# garden.net
KiCad netlist of a schematic drawn in EAGLE
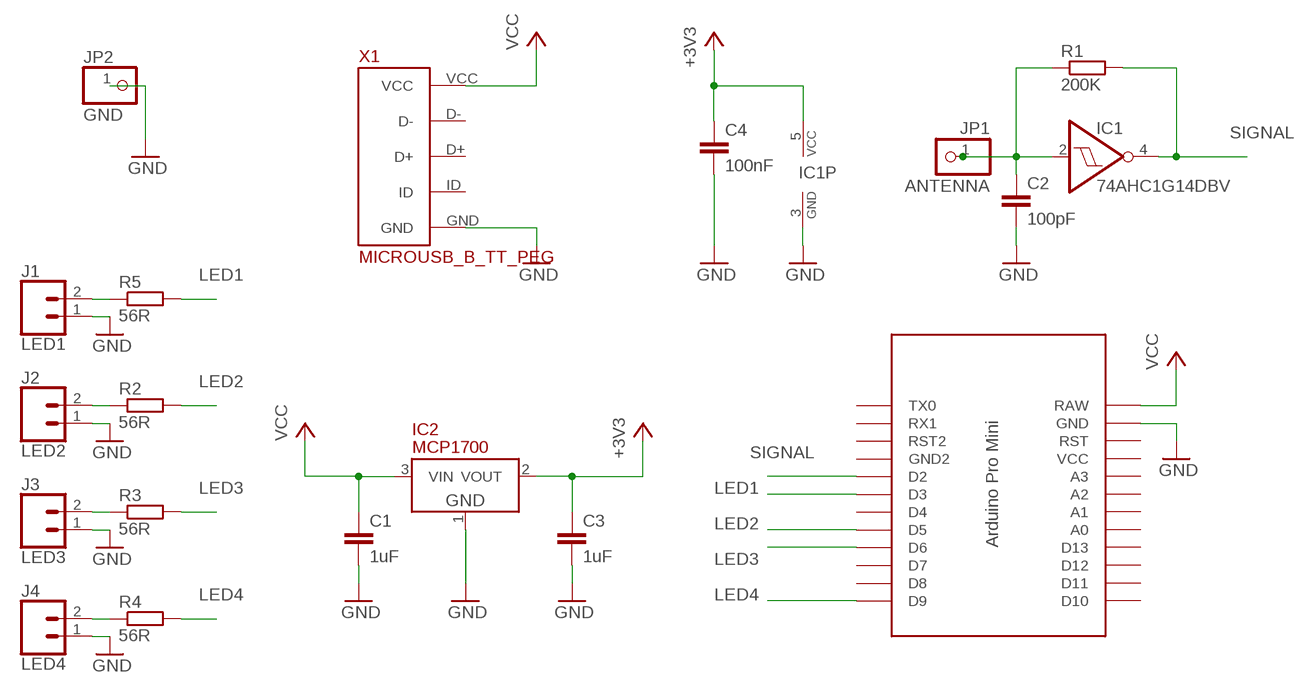
[diagram p0: schematic, sheet 1]

(export (version "E")
  (design (tool "Eeschema 10.0.6"))
  (components
    (comp (ref "C1")
      (value "1uF")
      (footprint "eagle-import:C0805")
      (libsource (lib "eagle-import") (part "C-EUC0805"))
    )
    (comp (ref "C2")
      (value "100pF")
      (footprint "eagle-import:C0805")
      (libsource (lib "eagle-import") (part "C-EUC0805"))
    )
    (comp (ref "C3")
      (value "1uF")
      (footprint "eagle-import:C0805")
      (libsource (lib "eagle-import") (part "C-EUC0805"))
    )
    (comp (ref "C4")
      (value "100nF")
      (footprint "eagle-import:C0805")
      (libsource (lib "eagle-import") (part "C-EUC0805"))
    )
    (comp (ref "IC1")
      (value "74AHC1G14DBV")
      (footprint "eagle-import:SOT23-5")
      (libsource (lib "eagle-import") (part "741G14DBVAHC"))
    )
    (comp (ref "IC2")
      (value "MCP1700")
      (footprint "eagle-import:SOT-23")
      (libsource (lib "eagle-import") (part "MCP1700"))
    )
    (comp (ref "J1")
      (value "LED1")
      (footprint "eagle-import:1X02")
      (libsource (lib "eagle-import") (part "CONN_02"))
    )
    (comp (ref "J2")
      (value "LED2")
      (footprint "eagle-import:1X02")
      (libsource (lib "eagle-import") (part "CONN_02"))
    )
    (comp (ref "J3")
      (value "LED3")
      (footprint "eagle-import:1X02")
      (libsource (lib "eagle-import") (part "CONN_02"))
    )
    (comp (ref "J4")
      (value "LED4")
      (footprint "eagle-import:1X02")
      (libsource (lib "eagle-import") (part "CONN_02"))
    )
    (comp (ref "JP1")
      (value "ANTENNA")
      (footprint "eagle-import:1X01")
      (libsource (lib "eagle-import") (part "PINHD-1X1"))
    )
    (comp (ref "JP2")
      (value "GND")
      (footprint "eagle-import:1X01")
      (libsource (lib "eagle-import") (part "PINHD-1X1"))
    )
    (comp (ref "R1")
      (value "200K")
      (footprint "eagle-import:R0805")
      (libsource (lib "eagle-import") (part "resistor_R-EU_R0805"))
    )
    (comp (ref "R2")
      (value "56R")
      (footprint "eagle-import:M0805")
      (libsource (lib "eagle-import") (part "R-EU_M0805"))
    )
    (comp (ref "R3")
      (value "56R")
      (footprint "eagle-import:M0805")
      (libsource (lib "eagle-import") (part "R-EU_M0805"))
    )
    (comp (ref "R4")
      (value "56R")
      (footprint "eagle-import:M0805")
      (libsource (lib "eagle-import") (part "R-EU_M0805"))
    )
    (comp (ref "R5")
      (value "56R")
      (footprint "eagle-import:M0805")
      (libsource (lib "eagle-import") (part "R-EU_M0805"))
    )
    (comp (ref "U$1")
      (value "PRO-MINI-TWO-SIDES-ONLY")
      (footprint "eagle-import:PRO-MINI-TWO-SIDES-ONLY")
      (libsource (lib "eagle-import") (part "PRO-MINI-TWO-SIDES-ONLY"))
    )
    (comp (ref "X1")
      (value "MICROUSB_B_TT_PEG")
      (footprint "eagle-import:MICROUSB_B_TT_PEG")
      (libsource (lib "eagle-import") (part "MICROUSB_B_TT_PEG"))
    )
  )
  (nets
    (net (code "1") (name "+3V3") (class "Default")
      (node (ref "C3") (pin "1") (pinfunction "1_1") (pintype "passive"))
      (node (ref "C4") (pin "1") (pinfunction "1_1") (pintype "passive"))
      (node (ref "IC1") (pin "5") (pinfunction "VCC_5") (pintype "power_in"))
      (node (ref "IC2") (pin "2") (pinfunction "VOUT_2") (pintype "passive"))
    )
    (net (code "2") (name "/LED1") (class "Default")
      (node (ref "R5") (pin "2") (pinfunction "2_2") (pintype "passive"))
      (node (ref "U$1") (pin "D3") (pinfunction "D3_D3") (pintype "bidirectional"))
    )
    (net (code "3") (name "/LED2") (class "Default")
      (node (ref "R2") (pin "2") (pinfunction "2_2") (pintype "passive"))
      (node (ref "U$1") (pin "D5") (pinfunction "D5_D5") (pintype "bidirectional"))
    )
    (net (code "4") (name "/LED3") (class "Default")
      (node (ref "R3") (pin "2") (pinfunction "2_2") (pintype "passive"))
      (node (ref "U$1") (pin "D6") (pinfunction "D6_D6") (pintype "bidirectional"))
    )
    (net (code "5") (name "/LED4") (class "Default")
      (node (ref "R4") (pin "2") (pinfunction "2_2") (pintype "passive"))
      (node (ref "U$1") (pin "D9") (pinfunction "D9_D9") (pintype "bidirectional"))
    )
    (net (code "6") (name "/SIGNAL") (class "Default")
      (node (ref "IC1") (pin "4") (pinfunction "O_4") (pintype "output"))
      (node (ref "R1") (pin "2") (pinfunction "2_2") (pintype "passive"))
      (node (ref "U$1") (pin "D2") (pinfunction "D2_D2") (pintype "bidirectional"))
    )
    (net (code "7") (name "GND") (class "Default")
      (node (ref "C1") (pin "2") (pinfunction "2_2") (pintype "passive"))
      (node (ref "C2") (pin "2") (pinfunction "2_2") (pintype "passive"))
      (node (ref "C3") (pin "2") (pinfunction "2_2") (pintype "passive"))
      (node (ref "C4") (pin "2") (pinfunction "2_2") (pintype "passive"))
      (node (ref "IC1") (pin "3") (pinfunction "GND_3") (pintype "power_in"))
      (node (ref "IC2") (pin "1") (pinfunction "GND_1") (pintype "input"))
      (node (ref "J1") (pin "1") (pinfunction "1_1") (pintype "passive"))
      (node (ref "J2") (pin "1") (pinfunction "1_1") (pintype "passive"))
      (node (ref "J3") (pin "1") (pinfunction "1_1") (pintype "passive"))
      (node (ref "J4") (pin "1") (pinfunction "1_1") (pintype "passive"))
      (node (ref "JP2") (pin "1") (pinfunction "1_1") (pintype "passive"))
      (node (ref "U$1") (pin "GND") (pinfunction "GND_GND") (pintype "input"))
      (node (ref "X1") (pin "GND") (pinfunction "GND_GND") (pintype "power_in"))
    )
    (net (code "8") (name "Net-(IC1A-I)") (class "Default")
      (node (ref "C2") (pin "1") (pinfunction "1_1") (pintype "passive"))
      (node (ref "IC1") (pin "2") (pinfunction "I_2") (pintype "input"))
      (node (ref "JP1") (pin "1") (pinfunction "1_1") (pintype "passive"))
      (node (ref "R1") (pin "1") (pinfunction "1_1") (pintype "passive"))
    )
    (net (code "9") (name "Net-(J1-Pad2)") (class "Default")
      (node (ref "J1") (pin "2") (pinfunction "2_2") (pintype "passive"))
      (node (ref "R5") (pin "1") (pinfunction "1_1") (pintype "passive"))
    )
    (net (code "10") (name "Net-(J2-Pad2)") (class "Default")
      (node (ref "J2") (pin "2") (pinfunction "2_2") (pintype "passive"))
      (node (ref "R2") (pin "1") (pinfunction "1_1") (pintype "passive"))
    )
    (net (code "11") (name "Net-(J3-Pad2)") (class "Default")
      (node (ref "J3") (pin "2") (pinfunction "2_2") (pintype "passive"))
      (node (ref "R3") (pin "1") (pinfunction "1_1") (pintype "passive"))
    )
    (net (code "12") (name "Net-(J4-Pad2)") (class "Default")
      (node (ref "J4") (pin "2") (pinfunction "2_2") (pintype "passive"))
      (node (ref "R4") (pin "1") (pinfunction "1_1") (pintype "passive"))
    )
    (net (code "13") (name "VCC") (class "Default")
      (node (ref "C1") (pin "1") (pinfunction "1_1") (pintype "passive"))
      (node (ref "IC2") (pin "3") (pinfunction "VIN_3") (pintype "input"))
      (node (ref "U$1") (pin "RAW") (pinfunction "RAW_RAW") (pintype "power_in"))
      (node (ref "X1") (pin "VCC") (pinfunction "VCC_VCC") (pintype "power_in"))
    )
    (net (code "14") (name "unconnected-(U$1-GND2-PadGND1)") (class "Default")
      (node (ref "U$1") (pin "GND1") (pinfunction "GND2_GND1") (pintype "bidirectional"))
    )
    (net (code "15") (name "unconnected-(U$1-PadA0)") (class "Default")
      (node (ref "U$1") (pin "A0") (pinfunction "A0_A0") (pintype "bidirectional"))
    )
    (net (code "16") (name "unconnected-(U$1-PadA1)") (class "Default")
      (node (ref "U$1") (pin "A1") (pinfunction "A1_A1") (pintype "bidirectional"))
    )
    (net (code "17") (name "unconnected-(U$1-PadA2)") (class "Default")
      (node (ref "U$1") (pin "A2") (pinfunction "A2_A2") (pintype "bidirectional"))
    )
    (net (code "18") (name "unconnected-(U$1-PadA3)") (class "Default")
      (node (ref "U$1") (pin "A3") (pinfunction "A3_A3") (pintype "bidirectional"))
    )
    (net (code "19") (name "unconnected-(U$1-PadD4)") (class "Default")
      (node (ref "U$1") (pin "D4") (pinfunction "D4_D4") (pintype "bidirectional"))
    )
    (net (code "20") (name "unconnected-(U$1-PadD7)") (class "Default")
      (node (ref "U$1") (pin "D7") (pinfunction "D7_D7") (pintype "bidirectional"))
    )
    (net (code "21") (name "unconnected-(U$1-PadD8)") (class "Default")
      (node (ref "U$1") (pin "D8") (pinfunction "D8_D8") (pintype "bidirectional"))
    )
    (net (code "22") (name "unconnected-(U$1-PadD10)") (class "Default")
      (node (ref "U$1") (pin "D10") (pinfunction "D10_D10") (pintype "bidirectional"))
    )
    (net (code "23") (name "unconnected-(U$1-PadD11)") (class "Default")
      (node (ref "U$1") (pin "D11") (pinfunction "D11_D11") (pintype "bidirectional"))
    )
    (net (code "24") (name "unconnected-(U$1-PadD12)") (class "Default")
      (node (ref "U$1") (pin "D12") (pinfunction "D12_D12") (pintype "bidirectional"))
    )
    (net (code "25") (name "unconnected-(U$1-PadD13)") (class "Default")
      (node (ref "U$1") (pin "D13") (pinfunction "D13_D13") (pintype "bidirectional"))
    )
    (net (code "26") (name "unconnected-(U$1-PadRST)") (class "Default")
      (node (ref "U$1") (pin "RST") (pinfunction "RST_RST") (pintype "bidirectional"))
    )
    (net (code "27") (name "unconnected-(U$1-PadRX1)") (class "Default")
      (node (ref "U$1") (pin "RX1") (pinfunction "RX1_RX1") (pintype "bidirectional"))
    )
    (net (code "28") (name "unconnected-(U$1-PadTX0)") (class "Default")
      (node (ref "U$1") (pin "TX0") (pinfunction "TX0_TX0") (pintype "bidirectional"))
    )
    (net (code "29") (name "unconnected-(U$1-PadVCC)") (class "Default")
      (node (ref "U$1") (pin "VCC") (pinfunction "VCC_VCC") (pintype "bidirectional"))
    )
    (net (code "30") (name "unconnected-(U$1-RST2-PadRST1)") (class "Default")
      (node (ref "U$1") (pin "RST1") (pinfunction "RST2_RST1") (pintype "bidirectional"))
    )
    (net (code "31") (name "unconnected-(X1-PadD+)") (class "Default")
      (node (ref "X1") (pin "D+") (pinfunction "D+_D+") (pintype "bidirectional"))
    )
    (net (code "32") (name "unconnected-(X1-PadD-)") (class "Default")
      (node (ref "X1") (pin "D-") (pinfunction "D-_D-") (pintype "bidirectional"))
    )
    (net (code "33") (name "unconnected-(X1-PadID)") (class "Default")
      (node (ref "X1") (pin "ID") (pinfunction "ID_ID") (pintype "bidirectional"))
    )
  )
)
